# dtb-222-24V-supply.net
KiCad netlist of a schematic drawn in Altium Designer
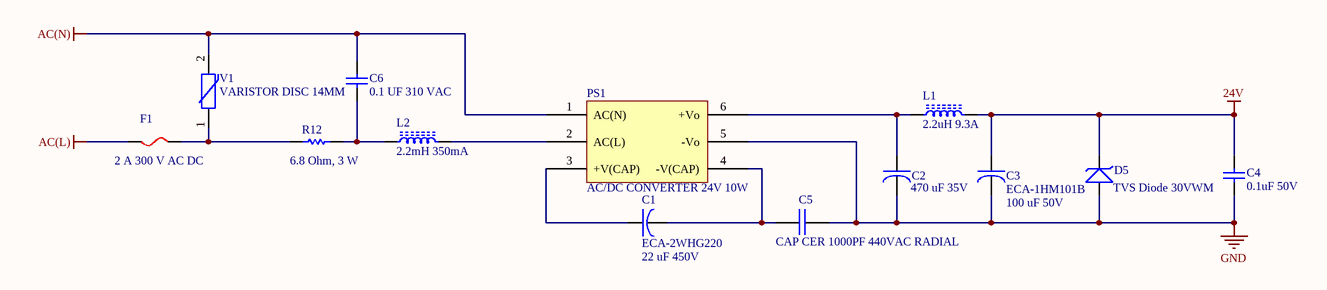
[diagram p0: dtb-222-24V-supply.SchDoc]

(export (version "E")
  (design (tool "Eeschema 10.0.6"))
  (components
    (comp (ref "C1")
      (value "ECA-2WHG220")
      (footprint "ECA-2WHG220")
      (description "22 µF 450 V Aluminum Electrolytic Capacitors Radial, Can 2000 Hrs @ 105°C")
      (fields
        (field (name "MANUFACTURER") "Panasonic Electronic Components")
        (field (name "ALTIUM_VALUE") "22 uF 450V")
      )
      (libsource (lib "andre-altium-lib") (part "ECA-2WHG220"))
    )
    (comp (ref "C2")
      (value "470 uF 35V")
      (footprint "35PX470MEFC10X12.5")
      (description "470 µF 35 V Aluminum Electrolytic Capacitors Radial, Can 2000 Hrs @ 105°C")
      (fields (field (name "MANUFACTURER") "Rubycon") (field (name "Comment") "35PX470MEFC10X12.5"))
      (libsource (lib "andre-altium-lib") (part "35PX470MEFC10X12.5"))
    )
    (comp (ref "C3")
      (value "ECA-1HM101B")
      (footprint "ECA-1HM101B")
      (description "100 µF 20% 50 V Aluminum Electrolytic Capacitors Radial, Can 2000 Hrs @ 85°C")
      (fields
        (field (name "MANUFACTURER") "Panasonic Electronic Components")
        (field (name "ALTIUM_VALUE") "100 uF 50V")
      )
      (libsource (lib "andre-altium-lib") (part "ECA-1HM101B"))
    )
    (comp (ref "C4")
      (value "0.1uF 50V")
      (footprint "Standard VoltServer 0603 Capacitor Footprint")
      (description "CAP CER 0.1UF 50V 10% X7R 0603")
      (fields (field (name "MANUFACTURER") "TDK") (field (name "Comment") "CGA3E2X7R1H104K080AE"))
      (libsource (lib "VoltServer Library") (part "CGA3E2X7R1H104K080AE"))
    )
    (comp (ref "C5")
      (value "CAP CER 1000PF 440VAC RADIAL")
      (footprint "CD45-E2GA102M-VKA")
      (description "1000 pF ±20% 440VAC Ceramic Capacitor E Radial, Disc")
      (fields (field (name "MANUFACTURER") "TDK Corporation"))
      (libsource (lib "andre-altium-lib") (part "CD45-E2GA102M-VKA"))
    )
    (comp (ref "C6")
      (value "0.1 UF 310 VAC")
      (footprint "890334023023CS")
      (description "0.1 µF Film Capacitor 310V Polypropylene (PP), Metallized Radial")
      (fields (field (name "MANUFACTURER") "Wurth Elektronik") (field (name "Comment") "CAP FILM 0.1UF 10%"))
      (libsource (lib "andre-altium-lib") (part "890334023023CS"))
    )
    (comp (ref "D5")
      (value "TVS Diode 30VWM")
      (footprint "SMBJ30A")
      (description "48.4V Clamp 12.4A Ipp Tvs Diode Surface Mount SMB (DO-214AA)")
      (fields
        (field (name "MANUFACTURER") "Bourns Inc.")
        (field (name "Comment") "TVS DIODE 30VWM 48.4VC SMB")
      )
      (libsource (lib "andre-altium-lib") (part "SMBJ30A"))
    )
    (comp (ref "F1")
      (value "2 A 300 V AC DC")
      (footprint "SS-5H-2A-APH")
      (description "2 A 300 V AC DC Fuse Board Mount (Cartridge Style Excluded) Through Hole Radial, Box")
      (fields (field (name "MANUFACTURER") "Eaton"))
      (libsource (lib "andre-altium-lib") (part "SS-5H-2A-APH"))
    )
    (comp (ref "L1")
      (value "2.2uH 9.3A")
      (footprint "0630CDMCCDS-2R2MC")
      (description "2.2 µH Shielded Molded Inductor 9.3 A 15mOhm Max Nonstandard")
      (fields
        (field (name "MANUFACTURER") "Sumida America Components Inc.")
        (field (name "Comment") "FIXED IND 2.2UH 9.3A 15MOHM SMD")
      )
      (libsource (lib "andre-altium-lib") (part "0630CDMCCDS-2R2MC"))
    )
    (comp (ref "L2")
      (value "2.2mH 350mA")
      (footprint "RLB1112V4-222J")
      (description "2.2 mH Unshielded Drum Core, Wirewound Inductor 350 mA 3.2Ohm Max Radial, Vertical Cylinder")
      (fields
        (field (name "MANUFACTURER") "Bourns Inc.")
        (field (name "Comment") "FIXED IND 2.2MH 350MA 3.2 OHM TH")
      )
      (libsource (lib "andre-altium-lib") (part "RLB1112V4-222J"))
    )
    (comp (ref "PS1")
      (value "AC/DC CONVERTER 24V 10W")
      (footprint "LS10-13B24R3")
      (description "Open Frame AC DC Converters 1 Output 24V 420mA 85 ~ 305 VAC, 100 ~ 430 VDC Input")
      (fields (field (name "MANUFACTURER") "Mornsun America, LLC"))
      (libsource (lib "andre-altium-lib") (part "LS10-13B24R3"))
    )
    (comp (ref "R12")
      (value "6.8 Ohm, 3 W")
      (footprint "AC03000006808JAC00")
      (fields
        (field (name "MANUFACTURER") "Vishay Beyschlag/Draloric/BB Components")
        (field (name "Comment") "RES 6.8 OHM 3W 5% AXIAL")
      )
      (libsource (lib "andre-altium-lib") (part "AC03000006808JAC00"))
    )
    (comp (ref "V1")
      (value "VARISTOR DISC 14MM")
      (footprint "B72214S0351K101")
      (description "560 V 4.5 kA Varistor 1 Circuit Through Hole Disc 14mm")
      (fields (field (name "MANUFACTURER") "EPCOS - TDK Electronics"))
      (libsource (lib "andre-altium-lib") (part "B72214S0351K101"))
    )
  )
  (nets
    (net (code "1") (name "24V") (class "Default")
      (node (ref "C3") (pin "1") (pinfunction "1_1") (pintype "passive"))
      (node (ref "C4") (pin "2") (pinfunction "2_2") (pintype "passive"))
      (node (ref "D5") (pin "1") (pinfunction "Cathode_1") (pintype "passive"))
      (node (ref "L1") (pin "2") (pinfunction "2_2") (pintype "passive"))
    )
    (net (code "2") (name "AC(L)") (class "Default")
      (node (ref "F1") (pin "1") (pinfunction "1_1") (pintype "passive"))
    )
    (net (code "3") (name "AC(N)") (class "Default")
      (node (ref "C6") (pin "2") (pinfunction "2_2") (pintype "passive"))
      (node (ref "PS1") (pin "1") (pinfunction "AC(N)_1") (pintype "passive"))
      (node (ref "V1") (pin "2") (pinfunction "2_2") (pintype "passive"))
    )
    (net (code "4") (name "GND") (class "Default")
      (node (ref "C2") (pin "2") (pinfunction "2_2") (pintype "passive"))
      (node (ref "C3") (pin "2") (pinfunction "2_2") (pintype "passive"))
      (node (ref "C4") (pin "1") (pinfunction "1_1") (pintype "passive"))
      (node (ref "C5") (pin "2") (pinfunction "2_2") (pintype "passive"))
      (node (ref "D5") (pin "2") (pinfunction "Anode_2") (pintype "passive"))
      (node (ref "PS1") (pin "5") (pinfunction "-Vo_5") (pintype "passive"))
    )
    (net (code "5") (name "Net-(C6-Pad1)") (class "Default")
      (node (ref "C6") (pin "1") (pinfunction "1_1") (pintype "passive"))
      (node (ref "L2") (pin "1") (pinfunction "1_1") (pintype "passive"))
      (node (ref "R12") (pin "2") (pinfunction "2_2") (pintype "passive"))
    )
    (net (code "6") (name "Net-(F1-Pad2)") (class "Default")
      (node (ref "F1") (pin "2") (pinfunction "2_2") (pintype "passive"))
      (node (ref "R12") (pin "1") (pinfunction "1_1") (pintype "passive"))
      (node (ref "V1") (pin "1") (pinfunction "1_1") (pintype "passive"))
    )
    (net (code "7") (name "Net-(PS1-+V(CAP))") (class "Default")
      (node (ref "C1") (pin "1") (pinfunction "1_1") (pintype "passive"))
      (node (ref "PS1") (pin "3") (pinfunction "+V(CAP)_3") (pintype "passive"))
    )
    (net (code "8") (name "Net-(PS1-+Vo)") (class "Default")
      (node (ref "C2") (pin "1") (pinfunction "1_1") (pintype "passive"))
      (node (ref "L1") (pin "1") (pinfunction "1_1") (pintype "passive"))
      (node (ref "PS1") (pin "6") (pinfunction "+Vo_6") (pintype "passive"))
    )
    (net (code "9") (name "Net-(PS1--V(CAP))") (class "Default")
      (node (ref "C1") (pin "2") (pinfunction "2_2") (pintype "passive"))
      (node (ref "C5") (pin "1") (pinfunction "1_1") (pintype "passive"))
      (node (ref "PS1") (pin "4") (pinfunction "-V(CAP)_4") (pintype "passive"))
    )
    (net (code "10") (name "Net-(PS1-AC(L))") (class "Default")
      (node (ref "L2") (pin "2") (pinfunction "2_2") (pintype "passive"))
      (node (ref "PS1") (pin "2") (pinfunction "AC(L)_2") (pintype "passive"))
    )
  )
)
